# SoC_pwr_2.net
KiCad netlist of a schematic drawn in Altium Designer
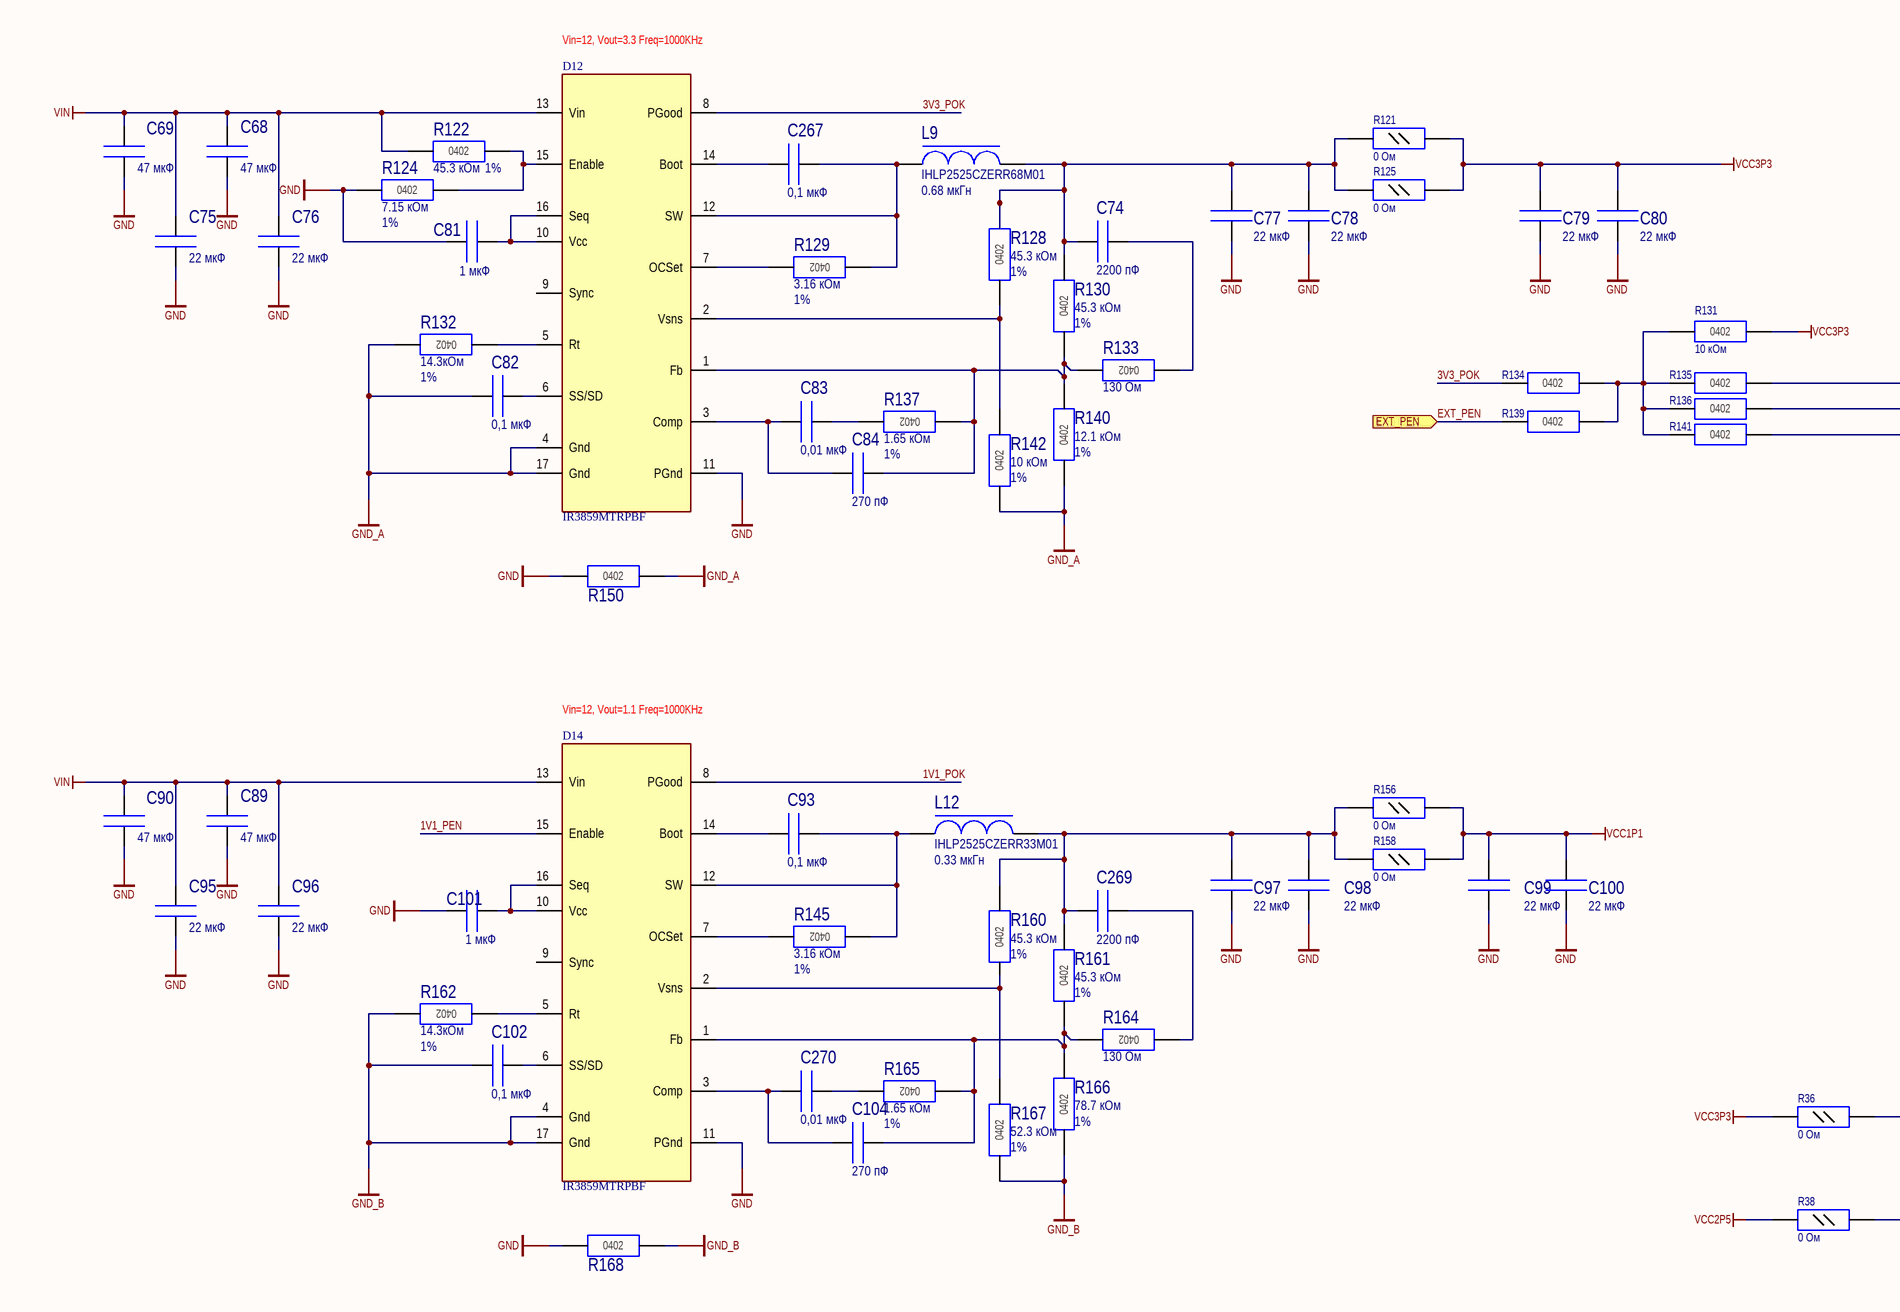
[diagram p0: SoC_pwr_2.SchDoc, left]
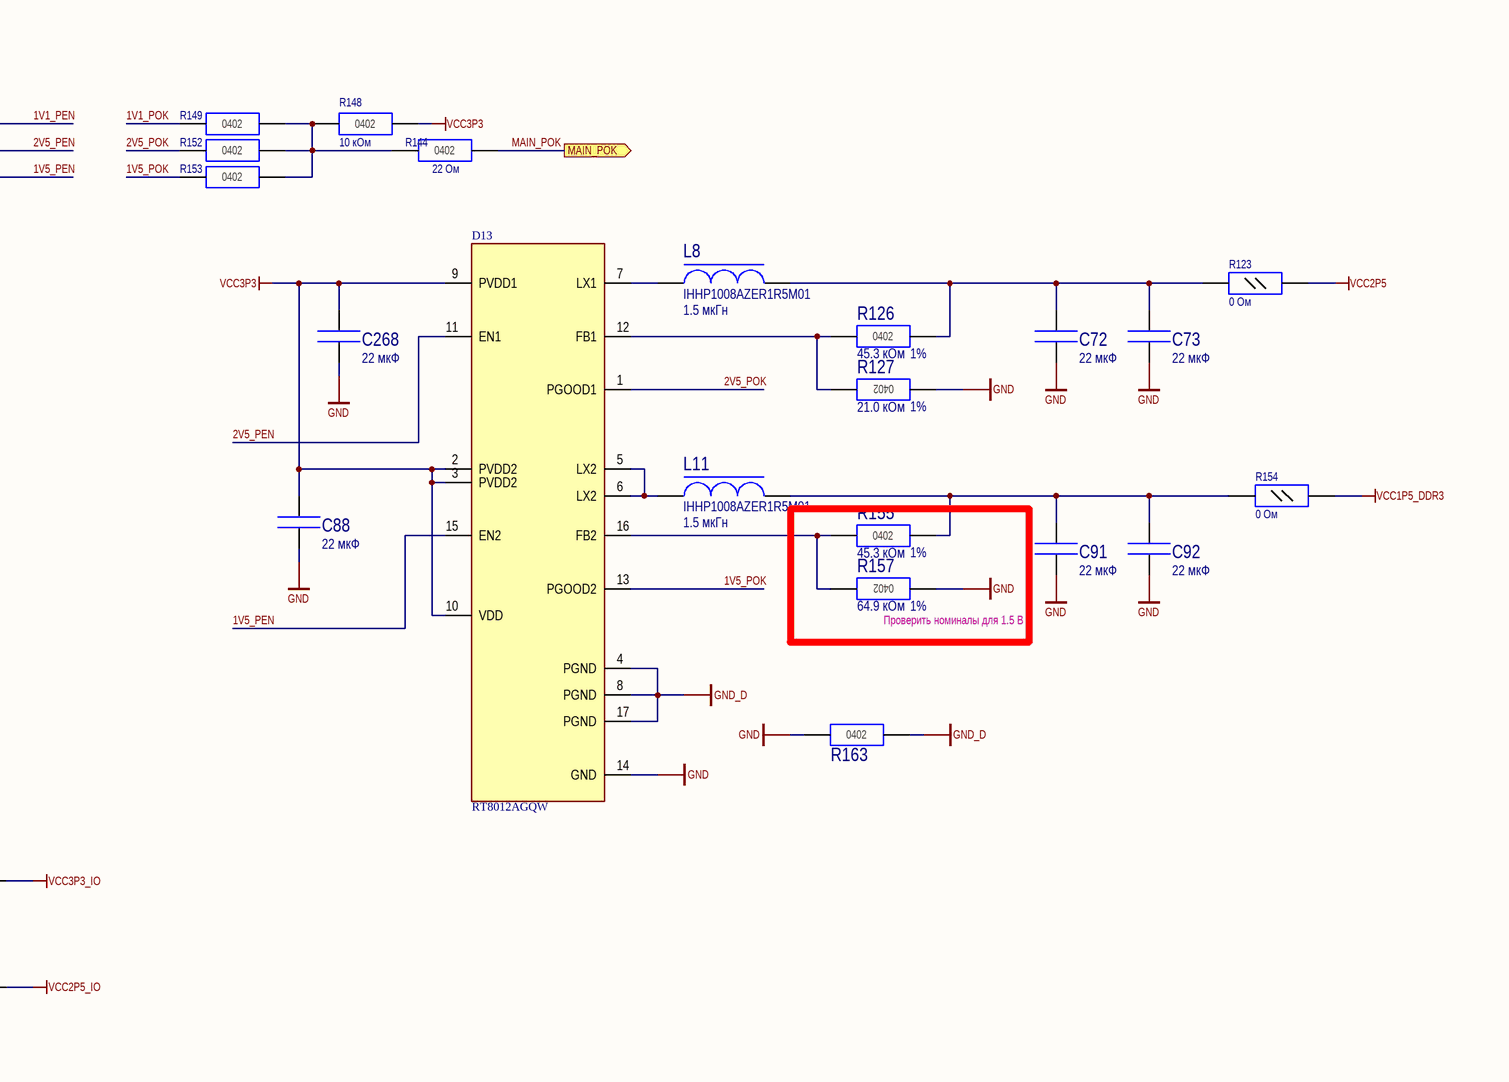
[diagram p1: SoC_pwr_2.SchDoc, right]

(export (version "E")
  (design (tool "Eeschema 10.0.6"))
  (components
    (comp (ref "C68")
      (value "47 мкФ")
      (footprint "CC0603")
      (description "Чип конденсатор керамический")
      (fields (field (name "Comment") "CC0603-X5R-47 мкФ-20%-6,3В"))
      (libsource (lib "Конденсаторы") (part "CC0603-X5R-#-20%-6,3В"))
    )
    (comp (ref "C69")
      (value "47 мкФ")
      (footprint "CC0603")
      (description "Чип конденсатор керамический")
      (fields (field (name "Comment") "CC0603-X5R-47 мкФ-20%-6,3В"))
      (libsource (lib "Конденсаторы") (part "CC0603-X5R-#-20%-6,3В"))
    )
    (comp (ref "C72")
      (value "22 мкФ")
      (footprint "CC0603")
      (description "Чип конденсатор керамический")
      (fields (field (name "Comment") "CC0603-X5R-22 мкФ-20%-6,3В"))
      (libsource (lib "Конденсаторы") (part "CC0603-X5R-#-20%-6,3В"))
    )
    (comp (ref "C73")
      (value "22 мкФ")
      (footprint "CC0603")
      (description "Чип конденсатор керамический")
      (fields (field (name "Comment") "CC0603-X5R-22 мкФ-20%-6,3В"))
      (libsource (lib "Конденсаторы") (part "CC0603-X5R-#-20%-6,3В"))
    )
    (comp (ref "C74")
      (value "2200 пФ")
      (footprint "CC0402(1005)")
      (description "Чип конденсатор керамический")
      (fields (field (name "Comment") "CC0402-X7R-2200 пФ-10%-16В"))
      (libsource (lib "Чип конденсаторы") (part "CC0402-X7R-#-20%-10В"))
    )
    (comp (ref "C75")
      (value "22 мкФ")
      (footprint "CC0603")
      (description "Чип конденсатор керамический")
      (fields (field (name "Comment") "CC0603-X5R-22 мкФ-20%-6,3В"))
      (libsource (lib "Конденсаторы") (part "CC0603-X5R-#-20%-6,3В"))
    )
    (comp (ref "C76")
      (value "22 мкФ")
      (footprint "CC0603")
      (description "Чип конденсатор керамический")
      (fields (field (name "Comment") "CC0603-X5R-22 мкФ-20%-6,3В"))
      (libsource (lib "Конденсаторы") (part "CC0603-X5R-#-20%-6,3В"))
    )
    (comp (ref "C77")
      (value "22 мкФ")
      (footprint "CC0603")
      (description "Чип конденсатор керамический")
      (fields (field (name "Comment") "CC0603-X5R-22 мкФ-20%-6,3В"))
      (libsource (lib "Конденсаторы") (part "CC0603-X5R-#-20%-6,3В"))
    )
    (comp (ref "C78")
      (value "22 мкФ")
      (footprint "CC0603")
      (description "Чип конденсатор керамический")
      (fields (field (name "Comment") "CC0603-X5R-22 мкФ-20%-6,3В"))
      (libsource (lib "Конденсаторы") (part "CC0603-X5R-#-20%-6,3В"))
    )
    (comp (ref "C79")
      (value "22 мкФ")
      (footprint "CC0603")
      (description "Чип конденсатор керамический")
      (fields (field (name "Comment") "CC0603-X5R-22 мкФ-20%-6,3В"))
      (libsource (lib "Конденсаторы") (part "CC0603-X5R-#-20%-6,3В"))
    )
    (comp (ref "C80")
      (value "22 мкФ")
      (footprint "CC0603")
      (description "Чип конденсатор керамический")
      (fields (field (name "Comment") "CC0603-X5R-22 мкФ-20%-6,3В"))
      (libsource (lib "Конденсаторы") (part "CC0603-X5R-#-20%-6,3В"))
    )
    (comp (ref "C81")
      (value "1 мкФ")
      (footprint "CC0603")
      (description "Чип конденсатор керамический")
      (fields (field (name "Comment") "CC0603-X5R-1 мкФ-10%-25В"))
      (libsource (lib "Конденсаторы") (part "CC0603-X5R-#-20%-6,3В"))
    )
    (comp (ref "C82")
      (value "0,1 мкФ")
      (footprint "CC0402(1005)")
      (description "Чип конденсатор керамический")
      (fields (field (name "Comment") "CC0402-X7R-0,1 мкФ-20%-10В"))
      (libsource (lib "Чип конденсаторы") (part "CC0402-X7R-#-20%-10В"))
    )
    (comp (ref "C83")
      (value "0,01 мкФ")
      (footprint "CC0402(1005)")
      (description "Чип конденсатор керамический")
      (fields (field (name "Comment") "CC0402-X7R-0,01 мкФ-10%-50В"))
      (libsource (lib "Чип конденсаторы") (part "CC0402-X7R-#-20%-10В"))
    )
    (comp (ref "C84")
      (value "270 пФ")
      (footprint "CC0402(1005)")
      (description "Чип конденсатор керамический")
      (fields (field (name "Comment") "CC0402-NP0-270 пФ-1%-50В"))
      (libsource (lib "Чип конденсаторы") (part "CC0402-X7R-#-20%-10В"))
    )
    (comp (ref "C88")
      (value "22 мкФ")
      (footprint "CC0603")
      (description "Чип конденсатор керамический")
      (fields (field (name "Comment") "CC0603-X5R-22 мкФ-20%-6,3В"))
      (libsource (lib "Конденсаторы") (part "CC0603-X5R-#-20%-6,3В"))
    )
    (comp (ref "C89")
      (value "47 мкФ")
      (footprint "CC0603")
      (description "Чип конденсатор керамический")
      (fields (field (name "Comment") "CC0603-X5R-47 мкФ-20%-6,3В"))
      (libsource (lib "Конденсаторы") (part "CC0603-X5R-#-20%-6,3В"))
    )
    (comp (ref "C90")
      (value "47 мкФ")
      (footprint "CC0603")
      (description "Чип конденсатор керамический")
      (fields (field (name "Comment") "CC0603-X5R-47 мкФ-20%-6,3В"))
      (libsource (lib "Конденсаторы") (part "CC0603-X5R-#-20%-6,3В"))
    )
    (comp (ref "C91")
      (value "22 мкФ")
      (footprint "CC0603")
      (description "Чип конденсатор керамический")
      (fields (field (name "Comment") "CC0603-X5R-22 мкФ-20%-6,3В"))
      (libsource (lib "Конденсаторы") (part "CC0603-X5R-#-20%-6,3В"))
    )
    (comp (ref "C92")
      (value "22 мкФ")
      (footprint "CC0603")
      (description "Чип конденсатор керамический")
      (fields (field (name "Comment") "CC0603-X5R-22 мкФ-20%-6,3В"))
      (libsource (lib "Конденсаторы") (part "CC0603-X5R-#-20%-6,3В"))
    )
    (comp (ref "C93")
      (value "0,1 мкФ")
      (footprint "CC0402(1005)")
      (description "Чип конденсатор керамический")
      (fields (field (name "Comment") "CC0402-X7R-0,1 мкФ-20%-10В"))
      (libsource (lib "Чип конденсаторы") (part "CC0402-X7R-#-20%-10В"))
    )
    (comp (ref "C95")
      (value "22 мкФ")
      (footprint "CC0603")
      (description "Чип конденсатор керамический")
      (fields (field (name "Comment") "CC0603-X5R-22 мкФ-20%-6,3В"))
      (libsource (lib "Конденсаторы") (part "CC0603-X5R-#-20%-6,3В"))
    )
    (comp (ref "C96")
      (value "22 мкФ")
      (footprint "CC0603")
      (description "Чип конденсатор керамический")
      (fields (field (name "Comment") "CC0603-X5R-22 мкФ-20%-6,3В"))
      (libsource (lib "Конденсаторы") (part "CC0603-X5R-#-20%-6,3В"))
    )
    (comp (ref "C97")
      (value "22 мкФ")
      (footprint "CC0603")
      (description "Чип конденсатор керамический")
      (fields (field (name "Comment") "CC0603-X5R-22 мкФ-20%-6,3В"))
      (libsource (lib "Конденсаторы") (part "CC0603-X5R-#-20%-6,3В"))
    )
    (comp (ref "C98")
      (value "22 мкФ")
      (footprint "CC0603")
      (description "Чип конденсатор керамический")
      (fields (field (name "Comment") "CC0603-X5R-22 мкФ-20%-6,3В"))
      (libsource (lib "Конденсаторы") (part "CC0603-X5R-#-20%-6,3В"))
    )
    (comp (ref "C99")
      (value "22 мкФ")
      (footprint "CC0603")
      (description "Чип конденсатор керамический")
      (fields (field (name "Comment") "CC0603-X5R-22 мкФ-20%-6,3В"))
      (libsource (lib "Конденсаторы") (part "CC0603-X5R-#-20%-6,3В"))
    )
    (comp (ref "C100")
      (value "22 мкФ")
      (footprint "CC0603")
      (description "Чип конденсатор керамический")
      (fields (field (name "Comment") "CC0603-X5R-22 мкФ-20%-6,3В"))
      (libsource (lib "Конденсаторы") (part "CC0603-X5R-#-20%-6,3В"))
    )
    (comp (ref "C101")
      (value "1 мкФ")
      (footprint "CC0603")
      (description "Чип конденсатор керамический")
      (fields (field (name "Comment") "CC0603-X5R-1 мкФ-10%-25В"))
      (libsource (lib "Конденсаторы") (part "CC0603-X5R-#-20%-6,3В"))
    )
    (comp (ref "C102")
      (value "0,1 мкФ")
      (footprint "CC0402(1005)")
      (description "Чип конденсатор керамический")
      (fields (field (name "Comment") "CC0402-X7R-0,1 мкФ-20%-10В"))
      (libsource (lib "Чип конденсаторы") (part "CC0402-X7R-#-20%-10В"))
    )
    (comp (ref "C104")
      (value "270 пФ")
      (footprint "CC0402(1005)")
      (description "Чип конденсатор керамический")
      (fields (field (name "Comment") "CC0402-NP0-270 пФ-1%-50В"))
      (libsource (lib "Чип конденсаторы") (part "CC0402-X7R-#-20%-10В"))
    )
    (comp (ref "C267")
      (value "0,1 мкФ")
      (footprint "CC0402(1005)")
      (description "Чип конденсатор керамический")
      (fields (field (name "Comment") "CC0402-X7R-0,1 мкФ-20%-10В"))
      (libsource (lib "Чип конденсаторы") (part "CC0402-X7R-#-20%-10В"))
    )
    (comp (ref "C268")
      (value "22 мкФ")
      (footprint "CC0603")
      (description "Чип конденсатор керамический")
      (fields (field (name "Comment") "CC0603-X5R-22 мкФ-20%-6,3В"))
      (libsource (lib "Конденсаторы") (part "CC0603-X5R-#-20%-6,3В"))
    )
    (comp (ref "C269")
      (value "2200 пФ")
      (footprint "CC0402(1005)")
      (description "Чип конденсатор керамический")
      (fields (field (name "Comment") "CC0402-X7R-2200 пФ-10%-16В"))
      (libsource (lib "Чип конденсаторы") (part "CC0402-X7R-#-20%-10В"))
    )
    (comp (ref "C270")
      (value "0,01 мкФ")
      (footprint "CC0402(1005)")
      (description "Чип конденсатор керамический")
      (fields (field (name "Comment") "CC0402-X7R-0,01 мкФ-10%-50В"))
      (libsource (lib "Чип конденсаторы") (part "CC0402-X7R-#-20%-10В"))
    )
    (comp (ref "D12")
      (value "IR3859MTRPBF")
      (footprint "IR3859")
      (description "IC REG BUCK ADJ 9A SYNC 17PQFN")
      (libsource (lib "SD_IC") (part "IR3859MPbF"))
    )
    (comp (ref "D13")
      (value "RT8012AGQW")
      (footprint "RT8012AGQW")
      (libsource (lib "SD_IC") (part "RT8012AGQW"))
    )
    (comp (ref "D14")
      (value "IR3859MTRPBF")
      (footprint "IR3859")
      (description "IC REG BUCK ADJ 9A SYNC 17PQFN")
      (libsource (lib "SD_IC") (part "IR3859MPbF"))
    )
    (comp (ref "L8")
      (value "IHHP1008AZER1R5M01")
      (footprint "INDC2720X12L")
      (description "FIXED IND 1.5UH 2.4A 96 MOHM SMD")
      (fields (field (name "ALTIUM_VALUE") "1.5 мкГн"))
      (libsource (lib "SD_IC") (part "L_VISH_IIHHP1008ABE_1"))
    )
    (comp (ref "L9")
      (value "IHLP2525CZERR68M01")
      (footprint "INDP6965X30L")
      (description "FIXED IND 680NH 15.5A 5.5 MOHM")
      (fields (field (name "ALTIUM_VALUE") "0.68 мкГн"))
      (libsource (lib "SD_IC") (part "L_VISH_IHLP2525CZERR68M01"))
    )
    (comp (ref "L11")
      (value "IHHP1008AZER1R5M01")
      (footprint "INDC2720X12L")
      (description "FIXED IND 1.5UH 2.4A 96 MOHM SMD")
      (fields (field (name "ALTIUM_VALUE") "1.5 мкГн"))
      (libsource (lib "SD_IC") (part "L_VISH_IIHHP1008ABE_1"))
    )
    (comp (ref "L12")
      (value "IHLP2525CZERR33M01")
      (footprint "INDP6965X30L")
      (description "FIXED IND 680NH 15.5A 5.5 MOHM")
      (fields (field (name "ALTIUM_VALUE") "0.33 мкГн"))
      (libsource (lib "SD_IC") (part "L_VISH_IHLP2525CZERR68M01"))
    )
    (comp (ref "R36")
      (value "0 Ом")
      (footprint "CR0805")
      (description "Чип резистор")
      (fields (field (name "Comment") "CR0805-0 Ом-±5%"))
      (libsource (lib "Резисторы") (part "CR0805-#-±5%"))
    )
    (comp (ref "R38")
      (value "0 Ом")
      (footprint "CR0805")
      (description "Чип резистор")
      (fields (field (name "Comment") "CR0805-0 Ом-±5%"))
      (libsource (lib "Резисторы") (part "CR0805-#-±5%"))
    )
    (comp (ref "R121")
      (value "0 Ом")
      (footprint "CR0805")
      (description "Чип резистор")
      (fields (field (name "Comment") "CR0805-0 Ом-±5%"))
      (libsource (lib "Резисторы") (part "CR0805-#-±5%"))
    )
    (comp (ref "R122")
      (value "45.3 кОм")
      (footprint "CR0402(1005)")
      (description "Чип резистор")
      (fields (field (name "TOLERANCE") "1%") (field (name "Comment") "CR0402-45.3 кОм-±1%"))
      (libsource (lib "") (part "CR0402-#-±1%_2"))
    )
    (comp (ref "R123")
      (value "0 Ом")
      (footprint "CR0805")
      (description "Чип резистор")
      (fields (field (name "Comment") "CR0805-0 Ом-±5%"))
      (libsource (lib "Резисторы") (part "CR0805-#-±5%"))
    )
    (comp (ref "R124")
      (value "7.15 кОм")
      (footprint "CR0402(1005)")
      (description "Чип резистор")
      (fields (field (name "TOLERANCE") "1%") (field (name "Comment") "CR0402-7.15 кОм-±1%"))
      (libsource (lib "") (part "CR0402-#-±1%_2"))
    )
    (comp (ref "R125")
      (value "0 Ом")
      (footprint "CR0805")
      (description "Чип резистор")
      (fields (field (name "Comment") "CR0805-0 Ом-±5%"))
      (libsource (lib "Резисторы") (part "CR0805-#-±5%"))
    )
    (comp (ref "R126")
      (value "45.3 кОм")
      (footprint "CR0402(1005)")
      (description "Чип резистор")
      (fields (field (name "TOLERANCE") "1%") (field (name "Comment") "CR0402-45.3 кОм-±1%"))
      (libsource (lib "") (part "CR0402-#-±1%_2"))
    )
    (comp (ref "R127")
      (value "21.0 кОм")
      (footprint "CR0402(1005)")
      (description "Чип резистор")
      (fields (field (name "TOLERANCE") "1%") (field (name "Comment") "CR0402-21.0 кОм-±1%"))
      (libsource (lib "Чип резисторы") (part "CR0402-#-±1%"))
    )
    (comp (ref "R128")
      (value "45.3 кОм")
      (footprint "CR0402(1005)")
      (description "Чип резистор")
      (fields (field (name "TOLERANCE") "1%") (field (name "Comment") "CR0402-45.3 кОм-±1%"))
      (libsource (lib "") (part "CR0402-#-±1%_1"))
    )
    (comp (ref "R129")
      (value "3.16 кОм")
      (footprint "CR0402(1005)")
      (description "Чип резистор")
      (fields (field (name "TOLERANCE") "1%") (field (name "Comment") "CR0402-3.16 кОм-±1%"))
      (libsource (lib "Чип резисторы") (part "CR0402-#-±1%"))
    )
    (comp (ref "R130")
      (value "45.3 кОм")
      (footprint "CR0402(1005)")
      (description "Чип резистор")
      (fields (field (name "TOLERANCE") "1%") (field (name "Comment") "CR0402-45.3 кОм-±1%"))
      (libsource (lib "") (part "CR0402-#-±1%_1"))
    )
    (comp (ref "R131")
      (value "10 кОм")
      (footprint "CR0402(1005)")
      (description "Чип резистор")
      (fields (field (name "TOLERANCE") "5%") (field (name "Comment") "CR0402-10 кОм-±5%"))
      (libsource (lib "Резисторы") (part "CR0402-#-±5%"))
    )
    (comp (ref "R132")
      (value "14.3кОм")
      (footprint "CR0402(1005)")
      (description "Чип резистор")
      (fields (field (name "TOLERANCE") "1%") (field (name "Comment") "CR0402-14.3кОм-±1%"))
      (libsource (lib "Чип резисторы") (part "CR0402-#-±1%"))
    )
    (comp (ref "R133")
      (value "130 Ом")
      (footprint "CR0402(1005)")
      (description "Чип резистор")
      (fields (field (name "Comment") "CR0402-130 Ом-±1%"))
      (libsource (lib "Чип резисторы") (part "CR0402-#-±1%"))
    )
    (comp (ref "R134")
      (value "CR0402-0 Ом-±5%")
      (footprint "CR0402(1005)")
      (description "Чип резистор")
      (fields (field (name "TOLERANCE") "5%"))
      (libsource (lib "Резисторы") (part "CR0402-#-±5%"))
    )
    (comp (ref "R135")
      (value "CR0402-0 Ом-±5%")
      (footprint "CR0402(1005)")
      (description "Чип резистор")
      (fields (field (name "TOLERANCE") "5%"))
      (libsource (lib "Резисторы") (part "CR0402-#-±5%"))
    )
    (comp (ref "R136")
      (value "CR0402-0 Ом-±5%")
      (footprint "CR0402(1005)")
      (description "Чип резистор")
      (fields (field (name "TOLERANCE") "5%"))
      (libsource (lib "Резисторы") (part "CR0402-#-±5%"))
    )
    (comp (ref "R137")
      (value "1.65 кОм")
      (footprint "CR0402(1005)")
      (description "Чип резистор")
      (fields (field (name "TOLERANCE") "1%") (field (name "Comment") "CR0402-1.65 кОм-±1%"))
      (libsource (lib "Чип резисторы") (part "CR0402-#-±1%"))
    )
    (comp (ref "R139")
      (value "CR0402-0 Ом-±5%")
      (footprint "CR0402(1005)")
      (description "Чип резистор")
      (fields (field (name "TOLERANCE") "5%"))
      (libsource (lib "Резисторы") (part "CR0402-#-±5%"))
    )
    (comp (ref "R140")
      (value "12.1 кОм")
      (footprint "CR0402(1005)")
      (description "Чип резистор")
      (fields (field (name "TOLERANCE") "1%") (field (name "Comment") "CR0402-12.1 кОм-±1%"))
      (libsource (lib "") (part "CR0402-#-±1%_1"))
    )
    (comp (ref "R141")
      (value "CR0402-0 Ом-±5%")
      (footprint "CR0402(1005)")
      (description "Чип резистор")
      (fields (field (name "TOLERANCE") "5%"))
      (libsource (lib "Резисторы") (part "CR0402-#-±5%"))
    )
    (comp (ref "R142")
      (value "10 кОм")
      (footprint "CR0402(1005)")
      (description "Чип резистор")
      (fields (field (name "TOLERANCE") "1%") (field (name "Comment") "CR0402-10 кОм-±1%"))
      (libsource (lib "") (part "CR0402-#-±1%_1"))
    )
    (comp (ref "R144")
      (value "22 Ом")
      (footprint "CR0402(1005)")
      (description "Чип резистор")
      (fields (field (name "TOLERANCE") "5%") (field (name "Comment") "CR0402-22 Ом-±5%"))
      (libsource (lib "Чип резисторы") (part "CR0402-#-±5%"))
    )
    (comp (ref "R145")
      (value "3.16 кОм")
      (footprint "CR0402(1005)")
      (description "Чип резистор")
      (fields (field (name "TOLERANCE") "1%") (field (name "Comment") "CR0402-3.16 кОм-±1%"))
      (libsource (lib "Чип резисторы") (part "CR0402-#-±1%"))
    )
    (comp (ref "R148")
      (value "10 кОм")
      (footprint "CR0402(1005)")
      (description "Чип резистор")
      (fields (field (name "TOLERANCE") "5%") (field (name "Comment") "CR0402-10 кОм-±5%"))
      (libsource (lib "Резисторы") (part "CR0402-#-±5%"))
    )
    (comp (ref "R149")
      (value "CR0402-0 Ом-±5%")
      (footprint "CR0402(1005)")
      (description "Чип резистор")
      (fields (field (name "TOLERANCE") "5%"))
      (libsource (lib "Резисторы") (part "CR0402-#-±5%"))
    )
    (comp (ref "R150")
      (value "CR0402-0 Ом-±5%")
      (footprint "CR0402(1005)")
      (description "Чип резистор")
      (fields (field (name "TOLERANCE") "5%"))
      (libsource (lib "Резисторы") (part "CR0402-#-±5%"))
    )
    (comp (ref "R152")
      (value "CR0402-0 Ом-±5%")
      (footprint "CR0402(1005)")
      (description "Чип резистор")
      (fields (field (name "TOLERANCE") "5%"))
      (libsource (lib "Резисторы") (part "CR0402-#-±5%"))
    )
    (comp (ref "R153")
      (value "CR0402-0 Ом-±5%")
      (footprint "CR0402(1005)")
      (description "Чип резистор")
      (fields (field (name "TOLERANCE") "5%"))
      (libsource (lib "Резисторы") (part "CR0402-#-±5%"))
    )
    (comp (ref "R154")
      (value "0 Ом")
      (footprint "CR0805")
      (description "Чип резистор")
      (fields (field (name "Comment") "CR0805-0 Ом-±5%"))
      (libsource (lib "Резисторы") (part "CR0805-#-±5%"))
    )
    (comp (ref "R155")
      (value "45.3 кОм")
      (footprint "CR0402(1005)")
      (description "Чип резистор")
      (fields (field (name "TOLERANCE") "1%") (field (name "Comment") "CR0402-45.3 кОм-±1%"))
      (libsource (lib "") (part "CR0402-#-±1%_2"))
    )
    (comp (ref "R156")
      (value "0 Ом")
      (footprint "CR0805")
      (description "Чип резистор")
      (fields (field (name "Comment") "CR0805-0 Ом-±5%"))
      (libsource (lib "Резисторы") (part "CR0805-#-±5%"))
    )
    (comp (ref "R157")
      (value "64.9 кОм")
      (footprint "CR0402(1005)")
      (description "Чип резистор")
      (fields (field (name "TOLERANCE") "1%") (field (name "Comment") "CR0402-64.9 кОм-±1%"))
      (libsource (lib "Чип резисторы") (part "CR0402-#-±1%"))
    )
    (comp (ref "R158")
      (value "0 Ом")
      (footprint "CR0805")
      (description "Чип резистор")
      (fields (field (name "Comment") "CR0805-0 Ом-±5%"))
      (libsource (lib "Резисторы") (part "CR0805-#-±5%"))
    )
    (comp (ref "R160")
      (value "45.3 кОм")
      (footprint "CR0402(1005)")
      (description "Чип резистор")
      (fields (field (name "TOLERANCE") "1%") (field (name "Comment") "CR0402-45.3 кОм-±1%"))
      (libsource (lib "") (part "CR0402-#-±1%_1"))
    )
    (comp (ref "R161")
      (value "45.3 кОм")
      (footprint "CR0402(1005)")
      (description "Чип резистор")
      (fields (field (name "TOLERANCE") "1%") (field (name "Comment") "CR0402-45.3 кОм-±1%"))
      (libsource (lib "") (part "CR0402-#-±1%_1"))
    )
    (comp (ref "R162")
      (value "14.3кОм")
      (footprint "CR0402(1005)")
      (description "Чип резистор")
      (fields (field (name "TOLERANCE") "1%") (field (name "Comment") "CR0402-14.3кОм-±1%"))
      (libsource (lib "Чип резисторы") (part "CR0402-#-±1%"))
    )
    (comp (ref "R163")
      (value "CR0402-0 Ом-±5%")
      (footprint "CR0402(1005)")
      (description "Чип резистор")
      (fields (field (name "TOLERANCE") "5%"))
      (libsource (lib "Резисторы") (part "CR0402-#-±5%"))
    )
    (comp (ref "R164")
      (value "130 Ом")
      (footprint "CR0402(1005)")
      (description "Чип резистор")
      (fields (field (name "Comment") "CR0402-130 Ом-±1%"))
      (libsource (lib "Чип резисторы") (part "CR0402-#-±1%"))
    )
    (comp (ref "R165")
      (value "1.65 кОм")
      (footprint "CR0402(1005)")
      (description "Чип резистор")
      (fields (field (name "TOLERANCE") "1%") (field (name "Comment") "CR0402-1.65 кОм-±1%"))
      (libsource (lib "Чип резисторы") (part "CR0402-#-±1%"))
    )
    (comp (ref "R166")
      (value "78.7 кОм")
      (footprint "CR0402(1005)")
      (description "Чип резистор")
      (fields (field (name "TOLERANCE") "1%") (field (name "Comment") "CR0402-78.7 кОм-±1%"))
      (libsource (lib "") (part "CR0402-#-±1%_1"))
    )
    (comp (ref "R167")
      (value "52.3 кОм")
      (footprint "CR0402(1005)")
      (description "Чип резистор")
      (fields (field (name "TOLERANCE") "1%") (field (name "Comment") "CR0402-52.3 кОм-±1%"))
      (libsource (lib "") (part "CR0402-#-±1%_1"))
    )
    (comp (ref "R168")
      (value "CR0402-0 Ом-±5%")
      (footprint "CR0402(1005)")
      (description "Чип резистор")
      (fields (field (name "TOLERANCE") "5%"))
      (libsource (lib "Резисторы") (part "CR0402-#-±5%"))
    )
  )
  (nets
    (net (code "1") (name "/1V1_PEN") (class "Default")
      (node (ref "D14") (pin "15") (pinfunction "Enable_15") (pintype "passive"))
      (node (ref "R135") (pin "2") (pinfunction "-_2") (pintype "passive"))
    )
    (net (code "2") (name "/1V1_POK") (class "Default")
      (node (ref "D14") (pin "8") (pinfunction "PGood_8") (pintype "passive"))
      (node (ref "R149") (pin "1") (pinfunction "+_1") (pintype "passive"))
    )
    (net (code "3") (name "/1V5_PEN") (class "Default")
      (node (ref "D13") (pin "15") (pinfunction "EN2_15") (pintype "passive"))
      (node (ref "R141") (pin "2") (pinfunction "-_2") (pintype "passive"))
    )
    (net (code "4") (name "/1V5_POK") (class "Default")
      (node (ref "D13") (pin "13") (pinfunction "PGOOD2_13") (pintype "passive"))
      (node (ref "R153") (pin "1") (pinfunction "+_1") (pintype "passive"))
    )
    (net (code "5") (name "/2V5_PEN") (class "Default")
      (node (ref "D13") (pin "11") (pinfunction "EN1_11") (pintype "passive"))
      (node (ref "R136") (pin "2") (pinfunction "-_2") (pintype "passive"))
    )
    (net (code "6") (name "/2V5_POK") (class "Default")
      (node (ref "D13") (pin "1") (pinfunction "PGOOD1_1") (pintype "passive"))
      (node (ref "R152") (pin "1") (pinfunction "+_1") (pintype "passive"))
    )
    (net (code "7") (name "/3V3_POK") (class "Default")
      (node (ref "D12") (pin "8") (pinfunction "PGood_8") (pintype "passive"))
      (node (ref "R134") (pin "1") (pinfunction "+_1") (pintype "passive"))
    )
    (net (code "8") (name "/EXT_PEN") (class "Default")
      (node (ref "R139") (pin "1") (pinfunction "+_1") (pintype "passive"))
    )
    (net (code "9") (name "/MAIN_POK") (class "Default")
      (node (ref "R144") (pin "2") (pinfunction "-_2") (pintype "passive"))
    )
    (net (code "10") (name "GND") (class "Default")
      (node (ref "C100") (pin "2") (pinfunction "-_2") (pintype "passive"))
      (node (ref "C101") (pin "1") (pinfunction "+_1") (pintype "passive"))
      (node (ref "C268") (pin "2") (pinfunction "-_2") (pintype "passive"))
      (node (ref "C68") (pin "2") (pinfunction "-_2") (pintype "passive"))
      (node (ref "C69") (pin "2") (pinfunction "-_2") (pintype "passive"))
      (node (ref "C72") (pin "2") (pinfunction "-_2") (pintype "passive"))
      (node (ref "C73") (pin "2") (pinfunction "-_2") (pintype "passive"))
      (node (ref "C75") (pin "2") (pinfunction "-_2") (pintype "passive"))
      (node (ref "C76") (pin "2") (pinfunction "-_2") (pintype "passive"))
      (node (ref "C77") (pin "2") (pinfunction "-_2") (pintype "passive"))
      (node (ref "C78") (pin "2") (pinfunction "-_2") (pintype "passive"))
      (node (ref "C79") (pin "2") (pinfunction "-_2") (pintype "passive"))
      (node (ref "C80") (pin "2") (pinfunction "-_2") (pintype "passive"))
      (node (ref "C81") (pin "1") (pinfunction "+_1") (pintype "passive"))
      (node (ref "C88") (pin "2") (pinfunction "-_2") (pintype "passive"))
      (node (ref "C89") (pin "2") (pinfunction "-_2") (pintype "passive"))
      (node (ref "C90") (pin "2") (pinfunction "-_2") (pintype "passive"))
      (node (ref "C91") (pin "2") (pinfunction "-_2") (pintype "passive"))
      (node (ref "C92") (pin "2") (pinfunction "-_2") (pintype "passive"))
      (node (ref "C95") (pin "2") (pinfunction "-_2") (pintype "passive"))
      (node (ref "C96") (pin "2") (pinfunction "-_2") (pintype "passive"))
      (node (ref "C97") (pin "2") (pinfunction "-_2") (pintype "passive"))
      (node (ref "C98") (pin "2") (pinfunction "-_2") (pintype "passive"))
      (node (ref "C99") (pin "2") (pinfunction "-_2") (pintype "passive"))
      (node (ref "D12") (pin "11") (pinfunction "PGnd_11") (pintype "passive"))
      (node (ref "D13") (pin "14") (pinfunction "GND_14") (pintype "passive"))
      (node (ref "D14") (pin "11") (pinfunction "PGnd_11") (pintype "passive"))
      (node (ref "R124") (pin "1") (pinfunction "+_1") (pintype "passive"))
      (node (ref "R127") (pin "1") (pinfunction "+_1") (pintype "passive"))
      (node (ref "R150") (pin "1") (pinfunction "+_1") (pintype "passive"))
      (node (ref "R157") (pin "1") (pinfunction "+_1") (pintype "passive"))
      (node (ref "R163") (pin "1") (pinfunction "+_1") (pintype "passive"))
      (node (ref "R168") (pin "1") (pinfunction "+_1") (pintype "passive"))
    )
    (net (code "11") (name "GND_A") (class "Default")
      (node (ref "C82") (pin "1") (pinfunction "+_1") (pintype "passive"))
      (node (ref "D12") (pin "17") (pinfunction "Gnd_17") (pintype "passive"))
      (node (ref "D12") (pin "4") (pinfunction "Gnd_4") (pintype "passive"))
      (node (ref "R132") (pin "2") (pinfunction "-_2") (pintype "passive"))
      (node (ref "R140") (pin "1") (pinfunction "+_1") (pintype "passive"))
      (node (ref "R142") (pin "1") (pinfunction "+_1") (pintype "passive"))
      (node (ref "R150") (pin "2") (pinfunction "-_2") (pintype "passive"))
    )
    (net (code "12") (name "GND_B") (class "Default")
      (node (ref "C102") (pin "1") (pinfunction "+_1") (pintype "passive"))
      (node (ref "D14") (pin "17") (pinfunction "Gnd_17") (pintype "passive"))
      (node (ref "D14") (pin "4") (pinfunction "Gnd_4") (pintype "passive"))
      (node (ref "R162") (pin "2") (pinfunction "-_2") (pintype "passive"))
      (node (ref "R166") (pin "1") (pinfunction "+_1") (pintype "passive"))
      (node (ref "R167") (pin "1") (pinfunction "+_1") (pintype "passive"))
      (node (ref "R168") (pin "2") (pinfunction "-_2") (pintype "passive"))
    )
    (net (code "13") (name "GND_D") (class "Default")
      (node (ref "D13") (pin "17") (pinfunction "PGND_17") (pintype "passive"))
      (node (ref "D13") (pin "4") (pinfunction "PGND_4") (pintype "passive"))
      (node (ref "D13") (pin "8") (pinfunction "PGND_8") (pintype "passive"))
      (node (ref "R163") (pin "2") (pinfunction "-_2") (pintype "passive"))
    )
    (net (code "14") (name "Net-(C72-+)") (class "Default")
      (node (ref "C72") (pin "1") (pinfunction "+_1") (pintype "passive"))
      (node (ref "C73") (pin "1") (pinfunction "+_1") (pintype "passive"))
      (node (ref "L8") (pin "2") (pinfunction "2_2") (pintype "passive"))
      (node (ref "R123") (pin "1") (pinfunction "+_1") (pintype "passive"))
      (node (ref "R126") (pin "2") (pinfunction "-_2") (pintype "passive"))
    )
    (net (code "15") (name "Net-(C74-+)") (class "Default")
      (node (ref "C74") (pin "1") (pinfunction "+_1") (pintype "passive"))
      (node (ref "R133") (pin "1") (pinfunction "+_1") (pintype "passive"))
    )
    (net (code "16") (name "Net-(C74--)") (class "Default")
      (node (ref "C74") (pin "2") (pinfunction "-_2") (pintype "passive"))
      (node (ref "C77") (pin "1") (pinfunction "+_1") (pintype "passive"))
      (node (ref "C78") (pin "1") (pinfunction "+_1") (pintype "passive"))
      (node (ref "L9") (pin "2") (pinfunction "2_2") (pintype "passive"))
      (node (ref "R121") (pin "1") (pinfunction "+_1") (pintype "passive"))
      (node (ref "R125") (pin "1") (pinfunction "+_1") (pintype "passive"))
      (node (ref "R128") (pin "2") (pinfunction "-_2") (pintype "passive"))
      (node (ref "R130") (pin "2") (pinfunction "-_2") (pintype "passive"))
    )
    (net (code "17") (name "Net-(C81--)") (class "Default")
      (node (ref "C81") (pin "2") (pinfunction "-_2") (pintype "passive"))
      (node (ref "D12") (pin "10") (pinfunction "Vcc_10") (pintype "passive"))
      (node (ref "D12") (pin "16") (pinfunction "Seq_16") (pintype "passive"))
    )
    (net (code "18") (name "Net-(C82--)") (class "Default")
      (node (ref "C82") (pin "2") (pinfunction "-_2") (pintype "passive"))
      (node (ref "D12") (pin "6") (pinfunction "SS/SD_6") (pintype "passive"))
    )
    (net (code "19") (name "Net-(C83-+)") (class "Default")
      (node (ref "C83") (pin "1") (pinfunction "+_1") (pintype "passive"))
      (node (ref "C84") (pin "2") (pinfunction "-_2") (pintype "passive"))
      (node (ref "D12") (pin "3") (pinfunction "Comp_3") (pintype "passive"))
    )
    (net (code "20") (name "Net-(C83--)") (class "Default")
      (node (ref "C83") (pin "2") (pinfunction "-_2") (pintype "passive"))
      (node (ref "R137") (pin "2") (pinfunction "-_2") (pintype "passive"))
    )
    (net (code "21") (name "Net-(C84-+)") (class "Default")
      (node (ref "C84") (pin "1") (pinfunction "+_1") (pintype "passive"))
      (node (ref "D12") (pin "1") (pinfunction "Fb_1") (pintype "passive"))
      (node (ref "R130") (pin "1") (pinfunction "+_1") (pintype "passive"))
      (node (ref "R133") (pin "2") (pinfunction "-_2") (pintype "passive"))
      (node (ref "R137") (pin "1") (pinfunction "+_1") (pintype "passive"))
      (node (ref "R140") (pin "2") (pinfunction "-_2") (pintype "passive"))
    )
    (net (code "22") (name "Net-(C91-+)") (class "Default")
      (node (ref "C91") (pin "1") (pinfunction "+_1") (pintype "passive"))
      (node (ref "C92") (pin "1") (pinfunction "+_1") (pintype "passive"))
      (node (ref "L11") (pin "2") (pinfunction "2_2") (pintype "passive"))
      (node (ref "R154") (pin "1") (pinfunction "+_1") (pintype "passive"))
      (node (ref "R155") (pin "2") (pinfunction "-_2") (pintype "passive"))
    )
    (net (code "23") (name "Net-(C93-+)") (class "Default")
      (node (ref "C93") (pin "1") (pinfunction "+_1") (pintype "passive"))
      (node (ref "D14") (pin "14") (pinfunction "Boot_14") (pintype "passive"))
    )
    (net (code "24") (name "Net-(C93--)") (class "Default")
      (node (ref "C93") (pin "2") (pinfunction "-_2") (pintype "passive"))
      (node (ref "D14") (pin "12") (pinfunction "SW_12") (pintype "passive"))
      (node (ref "L12") (pin "1") (pinfunction "1_1") (pintype "passive"))
      (node (ref "R145") (pin "1") (pinfunction "+_1") (pintype "passive"))
    )
    (net (code "25") (name "Net-(C101--)") (class "Default")
      (node (ref "C101") (pin "2") (pinfunction "-_2") (pintype "passive"))
      (node (ref "D14") (pin "10") (pinfunction "Vcc_10") (pintype "passive"))
      (node (ref "D14") (pin "16") (pinfunction "Seq_16") (pintype "passive"))
    )
    (net (code "26") (name "Net-(C102--)") (class "Default")
      (node (ref "C102") (pin "2") (pinfunction "-_2") (pintype "passive"))
      (node (ref "D14") (pin "6") (pinfunction "SS/SD_6") (pintype "passive"))
    )
    (net (code "27") (name "Net-(C104-+)") (class "Default")
      (node (ref "C104") (pin "1") (pinfunction "+_1") (pintype "passive"))
      (node (ref "D14") (pin "1") (pinfunction "Fb_1") (pintype "passive"))
      (node (ref "R161") (pin "1") (pinfunction "+_1") (pintype "passive"))
      (node (ref "R164") (pin "2") (pinfunction "-_2") (pintype "passive"))
      (node (ref "R165") (pin "1") (pinfunction "+_1") (pintype "passive"))
      (node (ref "R166") (pin "2") (pinfunction "-_2") (pintype "passive"))
    )
    (net (code "28") (name "Net-(C104--)") (class "Default")
      (node (ref "C104") (pin "2") (pinfunction "-_2") (pintype "passive"))
      (node (ref "C270") (pin "1") (pinfunction "+_1") (pintype "passive"))
      (node (ref "D14") (pin "3") (pinfunction "Comp_3") (pintype "passive"))
    )
    (net (code "29") (name "Net-(C267-+)") (class "Default")
      (node (ref "C267") (pin "1") (pinfunction "+_1") (pintype "passive"))
      (node (ref "D12") (pin "14") (pinfunction "Boot_14") (pintype "passive"))
    )
    (net (code "30") (name "Net-(C267--)") (class "Default")
      (node (ref "C267") (pin "2") (pinfunction "-_2") (pintype "passive"))
      (node (ref "D12") (pin "12") (pinfunction "SW_12") (pintype "passive"))
      (node (ref "L9") (pin "1") (pinfunction "1_1") (pintype "passive"))
      (node (ref "R129") (pin "1") (pinfunction "+_1") (pintype "passive"))
    )
    (net (code "31") (name "Net-(C269-+)") (class "Default")
      (node (ref "C269") (pin "1") (pinfunction "+_1") (pintype "passive"))
      (node (ref "R164") (pin "1") (pinfunction "+_1") (pintype "passive"))
    )
    (net (code "32") (name "Net-(C269--)") (class "Default")
      (node (ref "C269") (pin "2") (pinfunction "-_2") (pintype "passive"))
      (node (ref "C97") (pin "1") (pinfunction "+_1") (pintype "passive"))
      (node (ref "C98") (pin "1") (pinfunction "+_1") (pintype "passive"))
      (node (ref "L12") (pin "2") (pinfunction "2_2") (pintype "passive"))
      (node (ref "R156") (pin "1") (pinfunction "+_1") (pintype "passive"))
      (node (ref "R158") (pin "1") (pinfunction "+_1") (pintype "passive"))
      (node (ref "R160") (pin "2") (pinfunction "-_2") (pintype "passive"))
      (node (ref "R161") (pin "2") (pinfunction "-_2") (pintype "passive"))
    )
    (net (code "33") (name "Net-(C270--)") (class "Default")
      (node (ref "C270") (pin "2") (pinfunction "-_2") (pintype "passive"))
      (node (ref "R165") (pin "2") (pinfunction "-_2") (pintype "passive"))
    )
    (net (code "34") (name "Net-(D12-Enable)") (class "Default")
      (node (ref "D12") (pin "15") (pinfunction "Enable_15") (pintype "passive"))
      (node (ref "R122") (pin "2") (pinfunction "-_2") (pintype "passive"))
      (node (ref "R124") (pin "2") (pinfunction "-_2") (pintype "passive"))
    )
    (net (code "35") (name "Net-(D12-OCSet)") (class "Default")
      (node (ref "D12") (pin "7") (pinfunction "OCSet_7") (pintype "passive"))
      (node (ref "R129") (pin "2") (pinfunction "-_2") (pintype "passive"))
    )
    (net (code "36") (name "Net-(D12-Rt)") (class "Default")
      (node (ref "D12") (pin "5") (pinfunction "Rt_5") (pintype "passive"))
      (node (ref "R132") (pin "1") (pinfunction "+_1") (pintype "passive"))
    )
    (net (code "37") (name "Net-(D12-Vsns)") (class "Default")
      (node (ref "D12") (pin "2") (pinfunction "Vsns_2") (pintype "passive"))
      (node (ref "R128") (pin "1") (pinfunction "+_1") (pintype "passive"))
      (node (ref "R142") (pin "2") (pinfunction "-_2") (pintype "passive"))
    )
    (net (code "38") (name "Net-(D13-FB1)") (class "Default")
      (node (ref "D13") (pin "12") (pinfunction "FB1_12") (pintype "passive"))
      (node (ref "R126") (pin "1") (pinfunction "+_1") (pintype "passive"))
      (node (ref "R127") (pin "2") (pinfunction "-_2") (pintype "passive"))
    )
    (net (code "39") (name "Net-(D13-FB2)") (class "Default")
      (node (ref "D13") (pin "16") (pinfunction "FB2_16") (pintype "passive"))
      (node (ref "R155") (pin "1") (pinfunction "+_1") (pintype "passive"))
      (node (ref "R157") (pin "2") (pinfunction "-_2") (pintype "passive"))
    )
    (net (code "40") (name "Net-(D13-LX1)") (class "Default")
      (node (ref "D13") (pin "7") (pinfunction "LX1_7") (pintype "passive"))
      (node (ref "L8") (pin "1") (pinfunction "1_1") (pintype "passive"))
    )
    (net (code "41") (name "Net-(D13-LX2-Pad5)") (class "Default")
      (node (ref "D13") (pin "5") (pinfunction "LX2_5") (pintype "passive"))
      (node (ref "D13") (pin "6") (pinfunction "LX2_6") (pintype "passive"))
      (node (ref "L11") (pin "1") (pinfunction "1_1") (pintype "passive"))
    )
    (net (code "42") (name "Net-(D14-OCSet)") (class "Default")
      (node (ref "D14") (pin "7") (pinfunction "OCSet_7") (pintype "passive"))
      (node (ref "R145") (pin "2") (pinfunction "-_2") (pintype "passive"))
    )
    (net (code "43") (name "Net-(D14-Rt)") (class "Default")
      (node (ref "D14") (pin "5") (pinfunction "Rt_5") (pintype "passive"))
      (node (ref "R162") (pin "1") (pinfunction "+_1") (pintype "passive"))
    )
    (net (code "44") (name "Net-(D14-Vsns)") (class "Default")
      (node (ref "D14") (pin "2") (pinfunction "Vsns_2") (pintype "passive"))
      (node (ref "R160") (pin "1") (pinfunction "+_1") (pintype "passive"))
      (node (ref "R167") (pin "2") (pinfunction "-_2") (pintype "passive"))
    )
    (net (code "45") (name "Net-(R131-+)") (class "Default")
      (node (ref "R131") (pin "1") (pinfunction "+_1") (pintype "passive"))
      (node (ref "R134") (pin "2") (pinfunction "-_2") (pintype "passive"))
      (node (ref "R135") (pin "1") (pinfunction "+_1") (pintype "passive"))
      (node (ref "R136") (pin "1") (pinfunction "+_1") (pintype "passive"))
      (node (ref "R139") (pin "2") (pinfunction "-_2") (pintype "passive"))
      (node (ref "R141") (pin "1") (pinfunction "+_1") (pintype "passive"))
    )
    (net (code "46") (name "Net-(R144-+)") (class "Default")
      (node (ref "R144") (pin "1") (pinfunction "+_1") (pintype "passive"))
      (node (ref "R148") (pin "1") (pinfunction "+_1") (pintype "passive"))
      (node (ref "R149") (pin "2") (pinfunction "-_2") (pintype "passive"))
      (node (ref "R152") (pin "2") (pinfunction "-_2") (pintype "passive"))
      (node (ref "R153") (pin "2") (pinfunction "-_2") (pintype "passive"))
    )
    (net (code "47") (name "VCC1P1") (class "Default")
      (node (ref "C100") (pin "1") (pinfunction "+_1") (pintype "passive"))
      (node (ref "C99") (pin "1") (pinfunction "+_1") (pintype "passive"))
      (node (ref "R156") (pin "2") (pinfunction "-_2") (pintype "passive"))
      (node (ref "R158") (pin "2") (pinfunction "-_2") (pintype "passive"))
    )
    (net (code "48") (name "VCC1P5_DDR3") (class "Default")
      (node (ref "R154") (pin "2") (pinfunction "-_2") (pintype "passive"))
    )
    (net (code "49") (name "VCC2P5") (class "Default")
      (node (ref "R123") (pin "2") (pinfunction "-_2") (pintype "passive"))
      (node (ref "R38") (pin "1") (pinfunction "+_1") (pintype "passive"))
    )
    (net (code "50") (name "VCC2P5_IO") (class "Default")
      (node (ref "R38") (pin "2") (pinfunction "-_2") (pintype "passive"))
    )
    (net (code "51") (name "VCC3P3") (class "Default")
      (node (ref "C268") (pin "1") (pinfunction "+_1") (pintype "passive"))
      (node (ref "C79") (pin "1") (pinfunction "+_1") (pintype "passive"))
      (node (ref "C80") (pin "1") (pinfunction "+_1") (pintype "passive"))
      (node (ref "C88") (pin "1") (pinfunction "+_1") (pintype "passive"))
      (node (ref "D13") (pin "10") (pinfunction "VDD_10") (pintype "passive"))
      (node (ref "D13") (pin "2") (pinfunction "PVDD2_2") (pintype "passive"))
      (node (ref "D13") (pin "3") (pinfunction "PVDD2_3") (pintype "passive"))
      (node (ref "D13") (pin "9") (pinfunction "PVDD1_9") (pintype "passive"))
      (node (ref "R121") (pin "2") (pinfunction "-_2") (pintype "passive"))
      (node (ref "R125") (pin "2") (pinfunction "-_2") (pintype "passive"))
      (node (ref "R131") (pin "2") (pinfunction "-_2") (pintype "passive"))
      (node (ref "R148") (pin "2") (pinfunction "-_2") (pintype "passive"))
      (node (ref "R36") (pin "1") (pinfunction "+_1") (pintype "passive"))
    )
    (net (code "52") (name "VCC3P3_IO") (class "Default")
      (node (ref "R36") (pin "2") (pinfunction "-_2") (pintype "passive"))
    )
    (net (code "53") (name "VIN") (class "Default")
      (node (ref "C68") (pin "1") (pinfunction "+_1") (pintype "passive"))
      (node (ref "C69") (pin "1") (pinfunction "+_1") (pintype "passive"))
      (node (ref "C75") (pin "1") (pinfunction "+_1") (pintype "passive"))
      (node (ref "C76") (pin "1") (pinfunction "+_1") (pintype "passive"))
      (node (ref "C89") (pin "1") (pinfunction "+_1") (pintype "passive"))
      (node (ref "C90") (pin "1") (pinfunction "+_1") (pintype "passive"))
      (node (ref "C95") (pin "1") (pinfunction "+_1") (pintype "passive"))
      (node (ref "C96") (pin "1") (pinfunction "+_1") (pintype "passive"))
      (node (ref "D12") (pin "13") (pinfunction "Vin_13") (pintype "passive"))
      (node (ref "D14") (pin "13") (pinfunction "Vin_13") (pintype "passive"))
      (node (ref "R122") (pin "1") (pinfunction "+_1") (pintype "passive"))
    )
    (net (code "54") (name "unconnected-(D12-Sync-Pad9)") (class "Default")
      (node (ref "D12") (pin "9") (pinfunction "Sync_9") (pintype "passive"))
    )
    (net (code "55") (name "unconnected-(D14-Sync-Pad9)") (class "Default")
      (node (ref "D14") (pin "9") (pinfunction "Sync_9") (pintype "passive"))
    )
  )
)
